# microbean.net
KiCad netlist of a schematic drawn in EAGLE
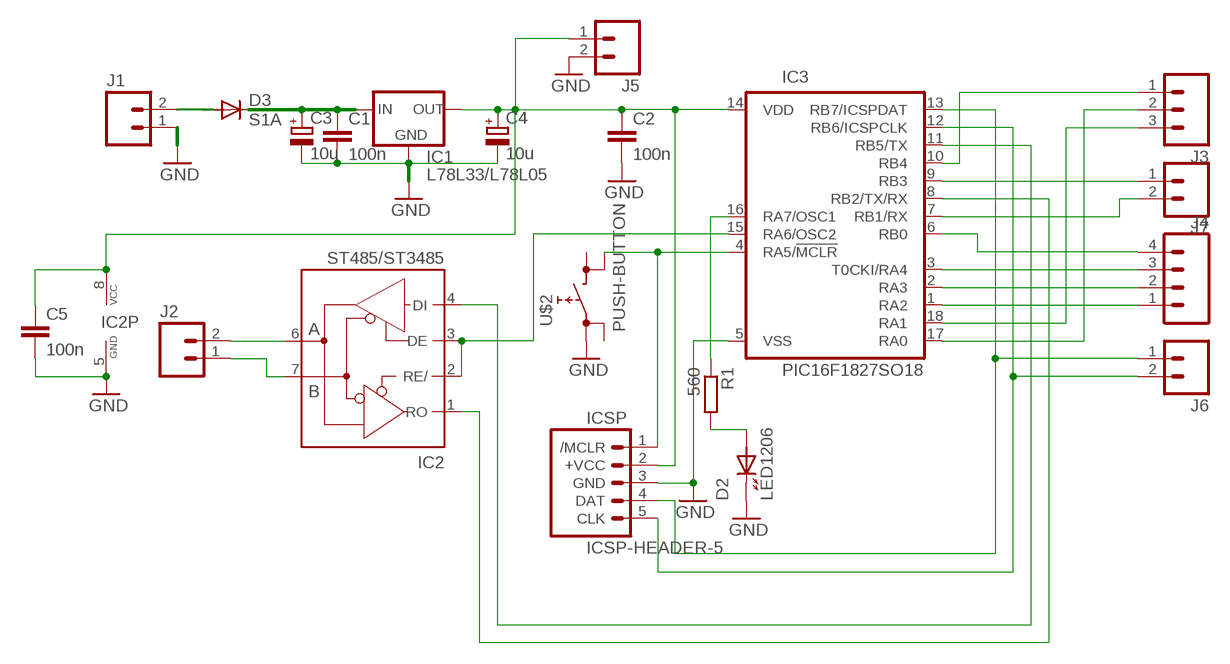
[diagram p0: schematic, sheet 1]

(export (version "E")
  (design (tool "Eeschema 10.0.6"))
  (components
    (comp (ref "C1")
      (value "100n")
      (footprint "eagle-import:C0805")
      (libsource (lib "eagle-import") (part "C-EUC0805"))
    )
    (comp (ref "C2")
      (value "100n")
      (footprint "eagle-import:C0805")
      (libsource (lib "eagle-import") (part "C-EUC0805"))
    )
    (comp (ref "C3")
      (value "10u")
      (footprint "eagle-import:UD-4X5,8_NICHICON")
      (libsource (lib "eagle-import") (part "CPOL-EUSMD4X5.3"))
    )
    (comp (ref "C4")
      (value "10u")
      (footprint "eagle-import:UD-4X5,8_NICHICON")
      (libsource (lib "eagle-import") (part "CPOL-EUSMD4X5.3"))
    )
    (comp (ref "C5")
      (value "100n")
      (footprint "eagle-import:C0805")
      (libsource (lib "eagle-import") (part "C-EUC0805"))
    )
    (comp (ref "D2")
      (value "LED1206")
      (footprint "eagle-import:CHIPLED_1206")
      (libsource (lib "eagle-import") (part "LED1206"))
    )
    (comp (ref "D3")
      (value "S1A")
      (footprint "eagle-import:SMA")
      (libsource (lib "eagle-import") (part "S1M"))
    )
    (comp (ref "IC1")
      (value "L78L33/L78L05")
      (footprint "eagle-import:SOT89")
      (libsource (lib "eagle-import") (part "78LXXSOT89"))
    )
    (comp (ref "IC2")
      (value "ST485/ST3485")
      (footprint "eagle-import:SO08")
      (libsource (lib "eagle-import") (part "MAX485ST3485"))
    )
    (comp (ref "IC3")
      (value "PIC16F1827SO18")
      (footprint "eagle-import:SO18W")
      (libsource (lib "eagle-import") (part "PIC16F1827SO18"))
    )
    (comp (ref "ICSP")
      (value "ICSP-HEADER-5")
      (footprint "eagle-import:1X05")
      (libsource (lib "eagle-import") (part "ICSP-HEADER-5"))
    )
    (comp (ref "J1")
      (value "M02-SCREW-3.5MM3.5MM")
      (footprint "eagle-import:SCREWTERMINAL-3.5MM-2")
      (libsource (lib "eagle-import") (part "M02-SCREW-3.5MM3.5MM"))
    )
    (comp (ref "J2")
      (value "M02-SCREW-3.5MM3.5MM")
      (footprint "eagle-import:SCREWTERMINAL-3.5MM-2")
      (libsource (lib "eagle-import") (part "M02-SCREW-3.5MM3.5MM"))
    )
    (comp (ref "J3")
      (value "M03")
      (footprint "eagle-import:1X03")
      (libsource (lib "eagle-import") (part "M03"))
    )
    (comp (ref "J4")
      (value "M04")
      (footprint "eagle-import:1X04")
      (libsource (lib "eagle-import") (part "M04"))
    )
    (comp (ref "J5")
      (value "M02")
      (footprint "eagle-import:1X02")
      (libsource (lib "eagle-import") (part "M02"))
    )
    (comp (ref "J6")
      (value "M02")
      (footprint "eagle-import:1X02")
      (libsource (lib "eagle-import") (part "M02"))
    )
    (comp (ref "J7")
      (value "M02")
      (footprint "eagle-import:1X02")
      (libsource (lib "eagle-import") (part "M02"))
    )
    (comp (ref "R1")
      (value "560")
      (footprint "eagle-import:R0805")
      (libsource (lib "eagle-import") (part "R-EU_R0805"))
    )
    (comp (ref "U$2")
      (value "PUSH-BUTTON")
      (footprint "eagle-import:MICRO-SWITCH")
      (libsource (lib "eagle-import") (part "PUSH-BUTTON"))
    )
  )
  (nets
    (net (code "1") (name "GND") (class "Default")
      (node (ref "C1") (pin "2") (pinfunction "2_2") (pintype "passive"))
      (node (ref "C2") (pin "2") (pinfunction "2_2") (pintype "passive"))
      (node (ref "C3") (pin "-") (pinfunction "-_-") (pintype "passive"))
      (node (ref "C4") (pin "-") (pinfunction "-_-") (pintype "passive"))
      (node (ref "C5") (pin "2") (pinfunction "2_2") (pintype "passive"))
      (node (ref "D2") (pin "C") (pinfunction "K_C") (pintype "passive"))
      (node (ref "IC1") (pin "2") (pinfunction "GND_2") (pintype "input"))
      (node (ref "IC1") (pin "2@1") (pinfunction "GND_2@1") (pintype "input"))
      (node (ref "IC2") (pin "5") (pinfunction "GND_5") (pintype "power_in"))
      (node (ref "IC3") (pin "5") (pinfunction "VSS_5") (pintype "power_in"))
      (node (ref "ICSP") (pin "3") (pinfunction "GND_3") (pintype "passive"))
      (node (ref "J1") (pin "1") (pinfunction "1_1") (pintype "passive"))
      (node (ref "J5") (pin "2") (pinfunction "2_2") (pintype "passive"))
      (node (ref "U$2") (pin "1") (pinfunction "0_1") (pintype "passive"))
    )
    (net (code "2") (name "Net-(D2-PadA)") (class "Default")
      (node (ref "D2") (pin "A") (pinfunction "A_A") (pintype "passive"))
      (node (ref "R1") (pin "2") (pinfunction "2_2") (pintype "passive"))
    )
    (net (code "3") (name "Net-(D3-PadA)") (class "Default")
      (node (ref "D3") (pin "A") (pinfunction "A_A") (pintype "passive"))
      (node (ref "J1") (pin "2") (pinfunction "2_2") (pintype "passive"))
    )
    (net (code "4") (name "Net-(IC1-IN)") (class "Default")
      (node (ref "C1") (pin "1") (pinfunction "1_1") (pintype "passive"))
      (node (ref "C3") (pin "+") (pinfunction "+_+") (pintype "passive"))
      (node (ref "D3") (pin "C") (pinfunction "C_C") (pintype "passive"))
      (node (ref "IC1") (pin "3") (pinfunction "IN_3") (pintype "input"))
    )
    (net (code "5") (name "Net-(IC1-OUT)") (class "Default")
      (node (ref "C2") (pin "1") (pinfunction "1_1") (pintype "passive"))
      (node (ref "C4") (pin "+") (pinfunction "+_+") (pintype "passive"))
      (node (ref "C5") (pin "1") (pinfunction "1_1") (pintype "passive"))
      (node (ref "IC1") (pin "1") (pinfunction "OUT_1") (pintype "passive"))
      (node (ref "IC2") (pin "8") (pinfunction "VCC_8") (pintype "power_in"))
      (node (ref "IC3") (pin "14") (pinfunction "VDD_14") (pintype "power_in"))
      (node (ref "ICSP") (pin "2") (pinfunction "+VCC_2") (pintype "passive"))
      (node (ref "J5") (pin "1") (pinfunction "1_1") (pintype "passive"))
    )
    (net (code "6") (name "Net-(IC2A-A)") (class "Default")
      (node (ref "IC2") (pin "6") (pinfunction "A_6") (pintype "passive"))
      (node (ref "J2") (pin "2") (pinfunction "2_2") (pintype "passive"))
    )
    (net (code "7") (name "Net-(IC2A-B)") (class "Default")
      (node (ref "IC2") (pin "7") (pinfunction "B_7") (pintype "passive"))
      (node (ref "J2") (pin "1") (pinfunction "1_1") (pintype "passive"))
    )
    (net (code "8") (name "Net-(IC2A-DE)") (class "Default")
      (node (ref "IC2") (pin "2") (pinfunction "RE/_2") (pintype "input"))
      (node (ref "IC2") (pin "3") (pinfunction "DE_3") (pintype "input"))
      (node (ref "IC3") (pin "15") (pinfunction "RA6/OSC2_15") (pintype "output"))
    )
    (net (code "9") (name "Net-(IC2A-DI)") (class "Default")
      (node (ref "IC2") (pin "4") (pinfunction "DI_4") (pintype "input"))
      (node (ref "IC3") (pin "11") (pinfunction "RB5/TX_11") (pintype "bidirectional"))
    )
    (net (code "10") (name "Net-(IC2A-RO)") (class "Default")
      (node (ref "IC2") (pin "1") (pinfunction "RO_1") (pintype "output"))
      (node (ref "IC3") (pin "8") (pinfunction "RB2/TX/RX_8") (pintype "bidirectional"))
    )
    (net (code "11") (name "Net-(IC3-RA0)") (class "Default")
      (node (ref "IC3") (pin "17") (pinfunction "RA0_17") (pintype "bidirectional"))
      (node (ref "J3") (pin "2") (pinfunction "2_2") (pintype "passive"))
    )
    (net (code "12") (name "Net-(IC3-RA1)") (class "Default")
      (node (ref "IC3") (pin "18") (pinfunction "RA1_18") (pintype "bidirectional"))
      (node (ref "J3") (pin "3") (pinfunction "3_3") (pintype "passive"))
    )
    (net (code "13") (name "Net-(IC3-RA2)") (class "Default")
      (node (ref "IC3") (pin "1") (pinfunction "RA2_1") (pintype "bidirectional"))
      (node (ref "J4") (pin "1") (pinfunction "1_1") (pintype "passive"))
    )
    (net (code "14") (name "Net-(IC3-RA3)") (class "Default")
      (node (ref "IC3") (pin "2") (pinfunction "RA3_2") (pintype "bidirectional"))
      (node (ref "J4") (pin "2") (pinfunction "2_2") (pintype "passive"))
    )
    (net (code "15") (name "Net-(IC3-RA5{slash}~{MCLR})") (class "Default")
      (node (ref "IC3") (pin "4") (pinfunction "RA5/~{MCLR}_4") (pintype "input"))
      (node (ref "ICSP") (pin "1") (pinfunction "/MCLR_1") (pintype "passive"))
      (node (ref "U$2") (pin "4") (pinfunction "1_4") (pintype "passive"))
    )
    (net (code "16") (name "Net-(IC3-RA7{slash}OSC1)") (class "Default")
      (node (ref "IC3") (pin "16") (pinfunction "RA7/OSC1_16") (pintype "input"))
      (node (ref "R1") (pin "1") (pinfunction "1_1") (pintype "passive"))
    )
    (net (code "17") (name "Net-(IC3-RB0)") (class "Default")
      (node (ref "IC3") (pin "6") (pinfunction "RB0_6") (pintype "bidirectional"))
      (node (ref "J4") (pin "4") (pinfunction "4_4") (pintype "passive"))
    )
    (net (code "18") (name "Net-(IC3-RB1{slash}RX)") (class "Default")
      (node (ref "IC3") (pin "7") (pinfunction "RB1/RX_7") (pintype "bidirectional"))
      (node (ref "J7") (pin "2") (pinfunction "2_2") (pintype "passive"))
    )
    (net (code "19") (name "Net-(IC3-RB3)") (class "Default")
      (node (ref "IC3") (pin "9") (pinfunction "RB3_9") (pintype "bidirectional"))
      (node (ref "J7") (pin "1") (pinfunction "1_1") (pintype "passive"))
    )
    (net (code "20") (name "Net-(IC3-RB4)") (class "Default")
      (node (ref "IC3") (pin "10") (pinfunction "RB4_10") (pintype "bidirectional"))
      (node (ref "J3") (pin "1") (pinfunction "1_1") (pintype "passive"))
    )
    (net (code "21") (name "Net-(IC3-RB6{slash}ICSPCLK)") (class "Default")
      (node (ref "IC3") (pin "12") (pinfunction "RB6/ICSPCLK_12") (pintype "bidirectional"))
      (node (ref "ICSP") (pin "5") (pinfunction "CLK_5") (pintype "passive"))
      (node (ref "J6") (pin "2") (pinfunction "2_2") (pintype "passive"))
    )
    (net (code "22") (name "Net-(IC3-RB7{slash}ICSPDAT)") (class "Default")
      (node (ref "IC3") (pin "13") (pinfunction "RB7/ICSPDAT_13") (pintype "bidirectional"))
      (node (ref "ICSP") (pin "4") (pinfunction "DAT_4") (pintype "passive"))
      (node (ref "J6") (pin "1") (pinfunction "1_1") (pintype "passive"))
    )
    (net (code "23") (name "Net-(IC3-T0CKI{slash}RA4)") (class "Default")
      (node (ref "IC3") (pin "3") (pinfunction "T0CKI/RA4_3") (pintype "bidirectional"))
      (node (ref "J4") (pin "3") (pinfunction "3_3") (pintype "passive"))
    )
    (net (code "24") (name "unconnected-(U$2-0-Pad2)") (class "Default")
      (node (ref "U$2") (pin "2") (pinfunction "0_2") (pintype "passive"))
    )
    (net (code "25") (name "unconnected-(U$2-1-Pad3)") (class "Default")
      (node (ref "U$2") (pin "3") (pinfunction "1_3") (pintype "passive"))
    )
  )
)
